# Vsense_0-69_3V.net
KiCad netlist of a schematic drawn in Altium Designer
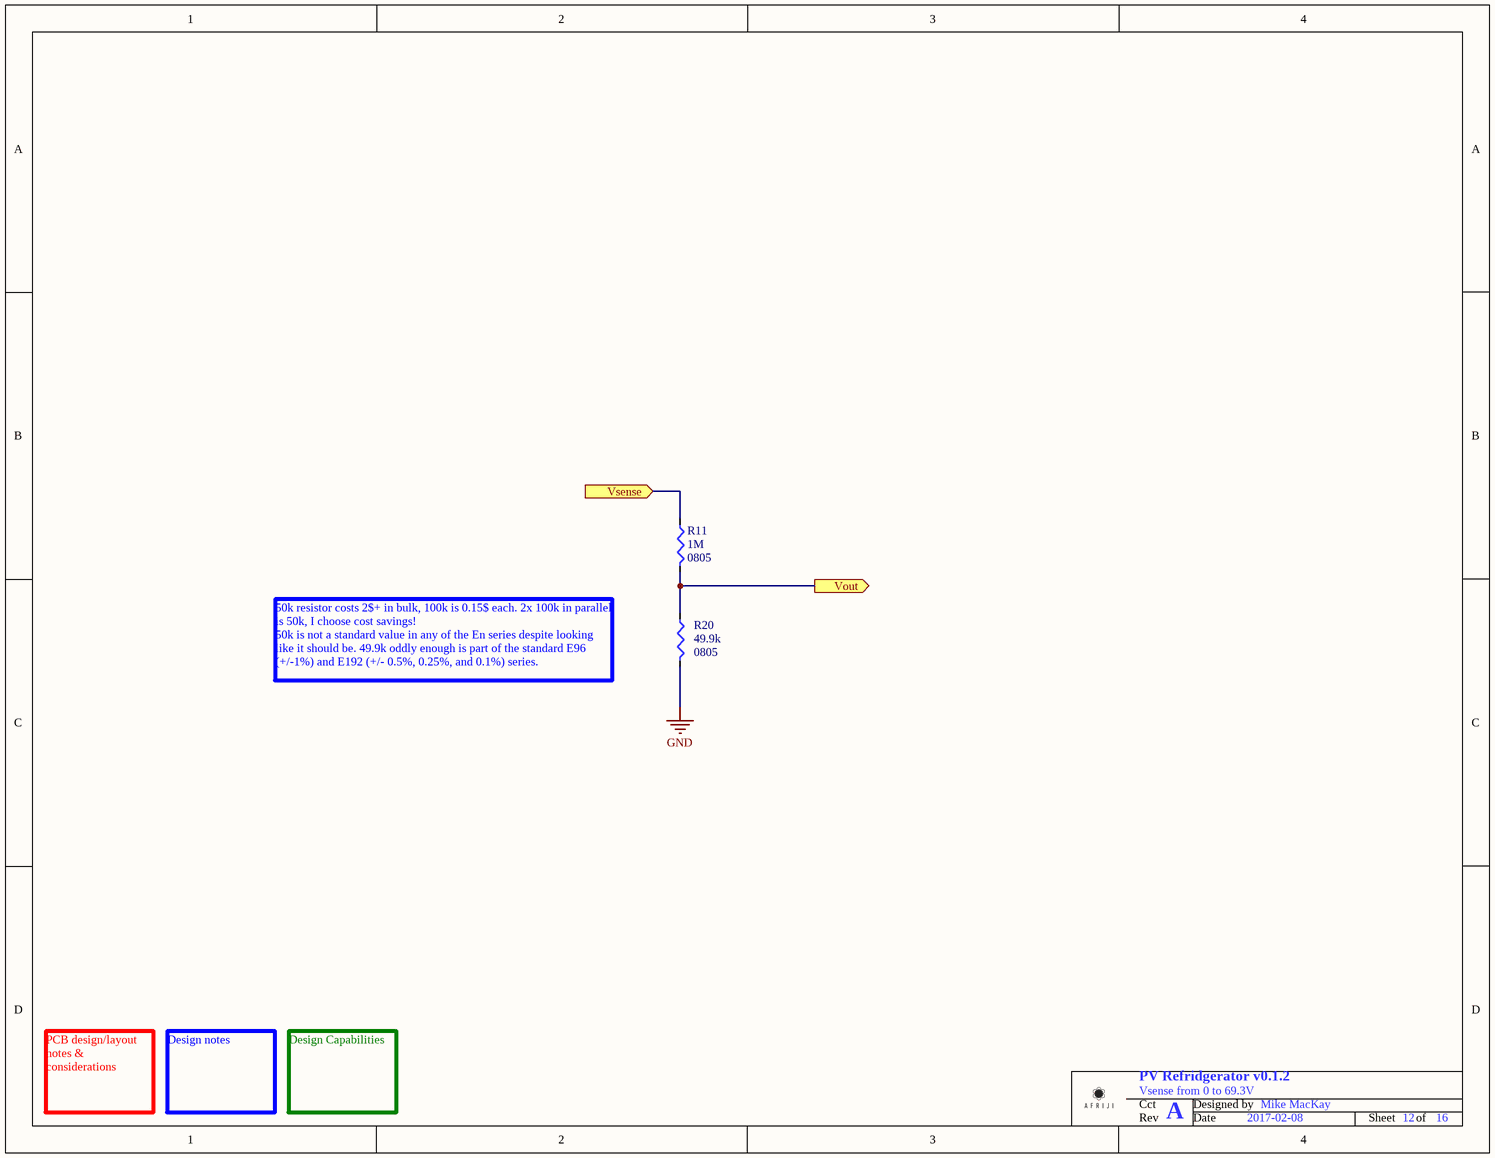
[diagram p0: Vsense 0-69.3V.SchDoc]

(export (version "E")
  (design (tool "Eeschema 10.0.6"))
  (components
    (comp (ref "R11")
      (value "Template - Resistor")
      (footprint "R0805")
      (description "Resistor")
      (fields
        (field (name "MANUFACTURER") "Yageo")
        (field (name "MANUFACTURER PART NUMBER") "RC0805FR-071ML")
        (field (name "RESISTANCE (OHMS)") "1M")
        (field (name "PACKAGE / CASE") "0805")
      )
      (libsource (lib "Integrated Component Library") (part "Template - Resistor"))
    )
    (comp (ref "R20")
      (value "Template - Resistor")
      (footprint "R0805")
      (fields
        (field (name "MANUFACTURER") "Yageo")
        (field (name "MANUFACTURER PART NUMBER") "RC0805FR-0749K9L")
        (field (name "RESISTANCE (OHMS)") "49.9k")
        (field (name "TOLERANCE") "±1%")
        (field (name "SUPPLIER DEVICE PACKAGE") "0805")
      )
      (libsource (lib "Personal Library") (part "Template - Resistor"))
    )
  )
  (nets
    (net (code "1") (name "/Vout") (class "Default")
      (node (ref "R11") (pin "1") (pinfunction "1_1") (pintype "passive"))
      (node (ref "R20") (pin "2") (pinfunction "2_2") (pintype "passive"))
    )
    (net (code "2") (name "/Vsense") (class "Default")
      (node (ref "R11") (pin "2") (pinfunction "2_2") (pintype "passive"))
    )
    (net (code "3") (name "GND") (class "Default")
      (node (ref "R20") (pin "1") (pinfunction "1_1") (pintype "passive"))
    )
  )
)
